# ProPrj__20260317_2026-03-17.net
KiCad netlist of a schematic drawn in EasyEDA Pro
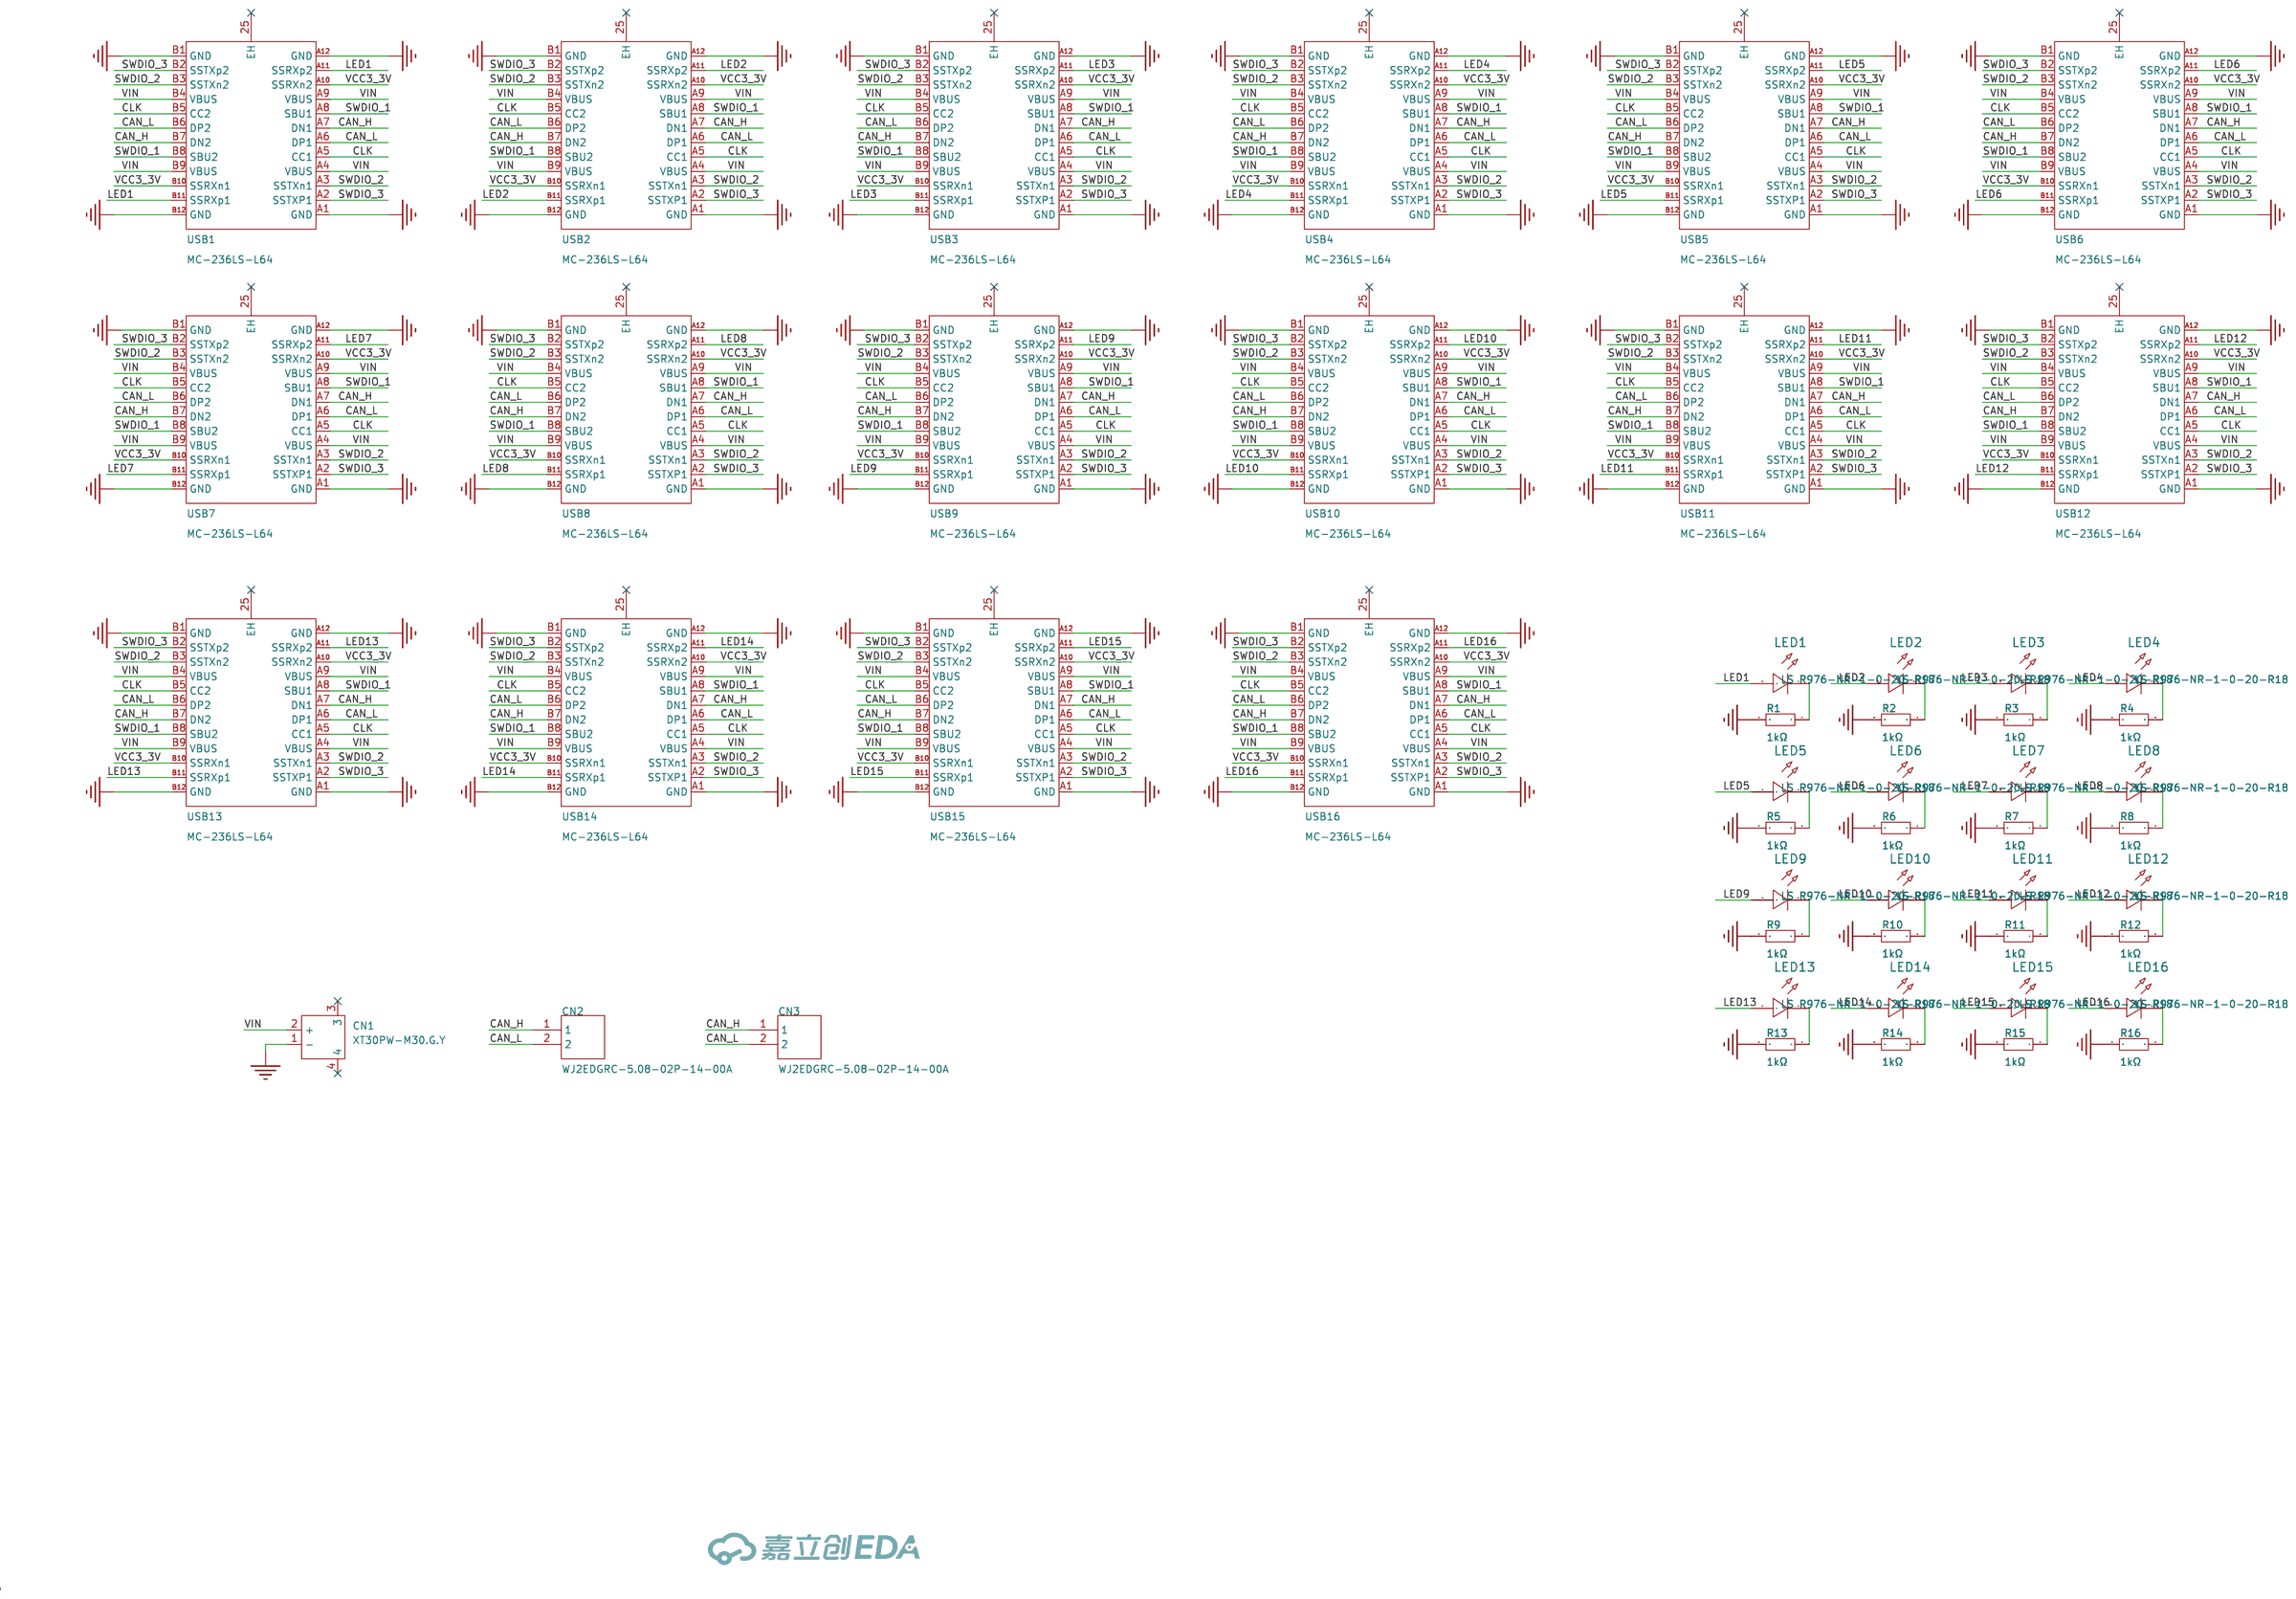
[diagram p0: schematic sheet]

(export (version "E")
  (design (tool "Eeschema 10.0.6"))
  (components
    (comp (ref "CN1")
      (value "XT30PW-M30.G.Y")
      (footprint "easyedapro:CONN-TH_XT30PW-M")
      (description "类别:-;类型1:-;")
      (fields (field (name "Manufacturer") "AMASS(艾迈斯)"))
      (libsource (lib "easyedapro") (part "XT30PW-M"))
    )
    (comp (ref "CN2")
      (value "WJ2EDGRC-5.08-02P-14-00A")
      (footprint "easyedapro:CONN-TH_2P-P5.08_WJ2EDGRC-5.08-2P")
      (fields (field (name "Manufacturer") "KANGNEX(康奈克斯电气)"))
      (libsource (lib "easyedapro") (part "WJ2EDGRC-5.08-2P"))
    )
    (comp (ref "CN3")
      (value "WJ2EDGRC-5.08-02P-14-00A")
      (footprint "easyedapro:CONN-TH_2P-P5.08_WJ2EDGRC-5.08-2P")
      (fields (field (name "Manufacturer") "KANGNEX(康奈克斯电气)"))
      (libsource (lib "easyedapro") (part "WJ2EDGRC-5.08-2P"))
    )
    (comp (ref "LED1")
      (value "LS R976-NR-1-0-20-R18")
      (footprint "easyedapro:LED_0805")
      (fields (field (name "Manufacturer") "OSRAM(欧司朗)"))
      (libsource (lib "easyedapro") (part "LED_R"))
    )
    (comp (ref "LED2")
      (value "LS R976-NR-1-0-20-R18")
      (footprint "easyedapro:LED_0805")
      (fields (field (name "Manufacturer") "OSRAM(欧司朗)"))
      (libsource (lib "easyedapro") (part "LED_R"))
    )
    (comp (ref "LED3")
      (value "LS R976-NR-1-0-20-R18")
      (footprint "easyedapro:LED_0805")
      (fields (field (name "Manufacturer") "OSRAM(欧司朗)"))
      (libsource (lib "easyedapro") (part "LED_R"))
    )
    (comp (ref "LED4")
      (value "LS R976-NR-1-0-20-R18")
      (footprint "easyedapro:LED_0805")
      (fields (field (name "Manufacturer") "OSRAM(欧司朗)"))
      (libsource (lib "easyedapro") (part "LED_R"))
    )
    (comp (ref "LED5")
      (value "LS R976-NR-1-0-20-R18")
      (footprint "easyedapro:LED_0805")
      (fields (field (name "Manufacturer") "OSRAM(欧司朗)"))
      (libsource (lib "easyedapro") (part "LED_R"))
    )
    (comp (ref "LED6")
      (value "LS R976-NR-1-0-20-R18")
      (footprint "easyedapro:LED_0805")
      (fields (field (name "Manufacturer") "OSRAM(欧司朗)"))
      (libsource (lib "easyedapro") (part "LED_R"))
    )
    (comp (ref "LED7")
      (value "LS R976-NR-1-0-20-R18")
      (footprint "easyedapro:LED_0805")
      (fields (field (name "Manufacturer") "OSRAM(欧司朗)"))
      (libsource (lib "easyedapro") (part "LED_R"))
    )
    (comp (ref "LED8")
      (value "LS R976-NR-1-0-20-R18")
      (footprint "easyedapro:LED_0805")
      (fields (field (name "Manufacturer") "OSRAM(欧司朗)"))
      (libsource (lib "easyedapro") (part "LED_R"))
    )
    (comp (ref "LED9")
      (value "LS R976-NR-1-0-20-R18")
      (footprint "easyedapro:LED_0805")
      (fields (field (name "Manufacturer") "OSRAM(欧司朗)"))
      (libsource (lib "easyedapro") (part "LED_R"))
    )
    (comp (ref "LED10")
      (value "LS R976-NR-1-0-20-R18")
      (footprint "easyedapro:LED_0805")
      (fields (field (name "Manufacturer") "OSRAM(欧司朗)"))
      (libsource (lib "easyedapro") (part "LED_R"))
    )
    (comp (ref "LED11")
      (value "LS R976-NR-1-0-20-R18")
      (footprint "easyedapro:LED_0805")
      (fields (field (name "Manufacturer") "OSRAM(欧司朗)"))
      (libsource (lib "easyedapro") (part "LED_R"))
    )
    (comp (ref "LED12")
      (value "LS R976-NR-1-0-20-R18")
      (footprint "easyedapro:LED_0805")
      (fields (field (name "Manufacturer") "OSRAM(欧司朗)"))
      (libsource (lib "easyedapro") (part "LED_R"))
    )
    (comp (ref "LED13")
      (value "LS R976-NR-1-0-20-R18")
      (footprint "easyedapro:LED_0805")
      (fields (field (name "Manufacturer") "OSRAM(欧司朗)"))
      (libsource (lib "easyedapro") (part "LED_R"))
    )
    (comp (ref "LED14")
      (value "LS R976-NR-1-0-20-R18")
      (footprint "easyedapro:LED_0805")
      (fields (field (name "Manufacturer") "OSRAM(欧司朗)"))
      (libsource (lib "easyedapro") (part "LED_R"))
    )
    (comp (ref "LED15")
      (value "LS R976-NR-1-0-20-R18")
      (footprint "easyedapro:LED_0805")
      (fields (field (name "Manufacturer") "OSRAM(欧司朗)"))
      (libsource (lib "easyedapro") (part "LED_R"))
    )
    (comp (ref "LED16")
      (value "LS R976-NR-1-0-20-R18")
      (footprint "easyedapro:LED_0805")
      (fields (field (name "Manufacturer") "OSRAM(欧司朗)"))
      (libsource (lib "easyedapro") (part "LED_R"))
    )
    (comp (ref "R1")
      (value "1kΩ")
      (footprint "easyedapro:R0805")
      (fields
        (field (name "Manufacturer Part") "0805W8F1001T5E")
        (field (name "Manufacturer") "UNI-ROYAL(厚声)")
      )
      (libsource (lib "easyedapro") (part "电阻"))
    )
    (comp (ref "R2")
      (value "1kΩ")
      (footprint "easyedapro:R0805")
      (fields
        (field (name "Manufacturer Part") "0805W8F1001T5E")
        (field (name "Manufacturer") "UNI-ROYAL(厚声)")
      )
      (libsource (lib "easyedapro") (part "电阻"))
    )
    (comp (ref "R3")
      (value "1kΩ")
      (footprint "easyedapro:R0805")
      (fields
        (field (name "Manufacturer Part") "0805W8F1001T5E")
        (field (name "Manufacturer") "UNI-ROYAL(厚声)")
      )
      (libsource (lib "easyedapro") (part "电阻"))
    )
    (comp (ref "R4")
      (value "1kΩ")
      (footprint "easyedapro:R0805")
      (fields
        (field (name "Manufacturer Part") "0805W8F1001T5E")
        (field (name "Manufacturer") "UNI-ROYAL(厚声)")
      )
      (libsource (lib "easyedapro") (part "电阻"))
    )
    (comp (ref "R5")
      (value "1kΩ")
      (footprint "easyedapro:R0805")
      (fields
        (field (name "Manufacturer Part") "0805W8F1001T5E")
        (field (name "Manufacturer") "UNI-ROYAL(厚声)")
      )
      (libsource (lib "easyedapro") (part "电阻"))
    )
    (comp (ref "R6")
      (value "1kΩ")
      (footprint "easyedapro:R0805")
      (fields
        (field (name "Manufacturer Part") "0805W8F1001T5E")
        (field (name "Manufacturer") "UNI-ROYAL(厚声)")
      )
      (libsource (lib "easyedapro") (part "电阻"))
    )
    (comp (ref "R7")
      (value "1kΩ")
      (footprint "easyedapro:R0805")
      (fields
        (field (name "Manufacturer Part") "0805W8F1001T5E")
        (field (name "Manufacturer") "UNI-ROYAL(厚声)")
      )
      (libsource (lib "easyedapro") (part "电阻"))
    )
    (comp (ref "R8")
      (value "1kΩ")
      (footprint "easyedapro:R0805")
      (fields
        (field (name "Manufacturer Part") "0805W8F1001T5E")
        (field (name "Manufacturer") "UNI-ROYAL(厚声)")
      )
      (libsource (lib "easyedapro") (part "电阻"))
    )
    (comp (ref "R9")
      (value "1kΩ")
      (footprint "easyedapro:R0805")
      (fields
        (field (name "Manufacturer Part") "0805W8F1001T5E")
        (field (name "Manufacturer") "UNI-ROYAL(厚声)")
      )
      (libsource (lib "easyedapro") (part "电阻"))
    )
    (comp (ref "R10")
      (value "1kΩ")
      (footprint "easyedapro:R0805")
      (fields
        (field (name "Manufacturer Part") "0805W8F1001T5E")
        (field (name "Manufacturer") "UNI-ROYAL(厚声)")
      )
      (libsource (lib "easyedapro") (part "电阻"))
    )
    (comp (ref "R11")
      (value "1kΩ")
      (footprint "easyedapro:R0805")
      (fields
        (field (name "Manufacturer Part") "0805W8F1001T5E")
        (field (name "Manufacturer") "UNI-ROYAL(厚声)")
      )
      (libsource (lib "easyedapro") (part "电阻"))
    )
    (comp (ref "R12")
      (value "1kΩ")
      (footprint "easyedapro:R0805")
      (fields
        (field (name "Manufacturer Part") "0805W8F1001T5E")
        (field (name "Manufacturer") "UNI-ROYAL(厚声)")
      )
      (libsource (lib "easyedapro") (part "电阻"))
    )
    (comp (ref "R13")
      (value "1kΩ")
      (footprint "easyedapro:R0805")
      (fields
        (field (name "Manufacturer Part") "0805W8F1001T5E")
        (field (name "Manufacturer") "UNI-ROYAL(厚声)")
      )
      (libsource (lib "easyedapro") (part "电阻"))
    )
    (comp (ref "R14")
      (value "1kΩ")
      (footprint "easyedapro:R0805")
      (fields
        (field (name "Manufacturer Part") "0805W8F1001T5E")
        (field (name "Manufacturer") "UNI-ROYAL(厚声)")
      )
      (libsource (lib "easyedapro") (part "电阻"))
    )
    (comp (ref "R15")
      (value "1kΩ")
      (footprint "easyedapro:R0805")
      (fields
        (field (name "Manufacturer Part") "0805W8F1001T5E")
        (field (name "Manufacturer") "UNI-ROYAL(厚声)")
      )
      (libsource (lib "easyedapro") (part "电阻"))
    )
    (comp (ref "R16")
      (value "1kΩ")
      (footprint "easyedapro:R0805")
      (fields
        (field (name "Manufacturer Part") "0805W8F1001T5E")
        (field (name "Manufacturer") "UNI-ROYAL(厚声)")
      )
      (libsource (lib "easyedapro") (part "电阻"))
    )
    (comp (ref "USB1")
      (value "MC-236LS-L64")
      (footprint "easyedapro:TYPE-C-USB-SMD_TYPE-C-31-M-06")
      (description "连接器类型:Type-C;协议标准:USB 3.1;公母:母;安装方式:立贴;触点数量:24P;端口数量:1;额定电流 - 电源:5A;工作温度:-25°C~+85°C;")
      (fields (field (name "Manufacturer") "HANBO(汉博)"))
      (libsource (lib "easyedapro") (part "MC-236LS-L64"))
    )
    (comp (ref "USB2")
      (value "MC-236LS-L64")
      (footprint "easyedapro:TYPE-C-USB-SMD_TYPE-C-31-M-06")
      (description "连接器类型:Type-C;协议标准:USB 3.1;公母:母;安装方式:立贴;触点数量:24P;端口数量:1;额定电流 - 电源:5A;工作温度:-25°C~+85°C;")
      (fields (field (name "Manufacturer") "HANBO(汉博)"))
      (libsource (lib "easyedapro") (part "MC-236LS-L64"))
    )
    (comp (ref "USB3")
      (value "MC-236LS-L64")
      (footprint "easyedapro:TYPE-C-USB-SMD_TYPE-C-31-M-06")
      (description "连接器类型:Type-C;协议标准:USB 3.1;公母:母;安装方式:立贴;触点数量:24P;端口数量:1;额定电流 - 电源:5A;工作温度:-25°C~+85°C;")
      (fields (field (name "Manufacturer") "HANBO(汉博)"))
      (libsource (lib "easyedapro") (part "MC-236LS-L64"))
    )
    (comp (ref "USB4")
      (value "MC-236LS-L64")
      (footprint "easyedapro:TYPE-C-USB-SMD_TYPE-C-31-M-06")
      (description "连接器类型:Type-C;协议标准:USB 3.1;公母:母;安装方式:立贴;触点数量:24P;端口数量:1;额定电流 - 电源:5A;工作温度:-25°C~+85°C;")
      (fields (field (name "Manufacturer") "HANBO(汉博)"))
      (libsource (lib "easyedapro") (part "MC-236LS-L64"))
    )
    (comp (ref "USB5")
      (value "MC-236LS-L64")
      (footprint "easyedapro:TYPE-C-USB-SMD_TYPE-C-31-M-06")
      (description "连接器类型:Type-C;协议标准:USB 3.1;公母:母;安装方式:立贴;触点数量:24P;端口数量:1;额定电流 - 电源:5A;工作温度:-25°C~+85°C;")
      (fields (field (name "Manufacturer") "HANBO(汉博)"))
      (libsource (lib "easyedapro") (part "MC-236LS-L64"))
    )
    (comp (ref "USB6")
      (value "MC-236LS-L64")
      (footprint "easyedapro:TYPE-C-USB-SMD_TYPE-C-31-M-06")
      (description "连接器类型:Type-C;协议标准:USB 3.1;公母:母;安装方式:立贴;触点数量:24P;端口数量:1;额定电流 - 电源:5A;工作温度:-25°C~+85°C;")
      (fields (field (name "Manufacturer") "HANBO(汉博)"))
      (libsource (lib "easyedapro") (part "MC-236LS-L64"))
    )
    (comp (ref "USB7")
      (value "MC-236LS-L64")
      (footprint "easyedapro:TYPE-C-USB-SMD_TYPE-C-31-M-06")
      (description "连接器类型:Type-C;协议标准:USB 3.1;公母:母;安装方式:立贴;触点数量:24P;端口数量:1;额定电流 - 电源:5A;工作温度:-25°C~+85°C;")
      (fields (field (name "Manufacturer") "HANBO(汉博)"))
      (libsource (lib "easyedapro") (part "MC-236LS-L64"))
    )
    (comp (ref "USB8")
      (value "MC-236LS-L64")
      (footprint "easyedapro:TYPE-C-USB-SMD_TYPE-C-31-M-06")
      (description "连接器类型:Type-C;协议标准:USB 3.1;公母:母;安装方式:立贴;触点数量:24P;端口数量:1;额定电流 - 电源:5A;工作温度:-25°C~+85°C;")
      (fields (field (name "Manufacturer") "HANBO(汉博)"))
      (libsource (lib "easyedapro") (part "MC-236LS-L64"))
    )
    (comp (ref "USB9")
      (value "MC-236LS-L64")
      (footprint "easyedapro:TYPE-C-USB-SMD_TYPE-C-31-M-06")
      (description "连接器类型:Type-C;协议标准:USB 3.1;公母:母;安装方式:立贴;触点数量:24P;端口数量:1;额定电流 - 电源:5A;工作温度:-25°C~+85°C;")
      (fields (field (name "Manufacturer") "HANBO(汉博)"))
      (libsource (lib "easyedapro") (part "MC-236LS-L64"))
    )
    (comp (ref "USB10")
      (value "MC-236LS-L64")
      (footprint "easyedapro:TYPE-C-USB-SMD_TYPE-C-31-M-06")
      (description "连接器类型:Type-C;协议标准:USB 3.1;公母:母;安装方式:立贴;触点数量:24P;端口数量:1;额定电流 - 电源:5A;工作温度:-25°C~+85°C;")
      (fields (field (name "Manufacturer") "HANBO(汉博)"))
      (libsource (lib "easyedapro") (part "MC-236LS-L64"))
    )
    (comp (ref "USB11")
      (value "MC-236LS-L64")
      (footprint "easyedapro:TYPE-C-USB-SMD_TYPE-C-31-M-06")
      (description "连接器类型:Type-C;协议标准:USB 3.1;公母:母;安装方式:立贴;触点数量:24P;端口数量:1;额定电流 - 电源:5A;工作温度:-25°C~+85°C;")
      (fields (field (name "Manufacturer") "HANBO(汉博)"))
      (libsource (lib "easyedapro") (part "MC-236LS-L64"))
    )
    (comp (ref "USB12")
      (value "MC-236LS-L64")
      (footprint "easyedapro:TYPE-C-USB-SMD_TYPE-C-31-M-06")
      (description "连接器类型:Type-C;协议标准:USB 3.1;公母:母;安装方式:立贴;触点数量:24P;端口数量:1;额定电流 - 电源:5A;工作温度:-25°C~+85°C;")
      (fields (field (name "Manufacturer") "HANBO(汉博)"))
      (libsource (lib "easyedapro") (part "MC-236LS-L64"))
    )
    (comp (ref "USB13")
      (value "MC-236LS-L64")
      (footprint "easyedapro:TYPE-C-USB-SMD_TYPE-C-31-M-06")
      (description "连接器类型:Type-C;协议标准:USB 3.1;公母:母;安装方式:立贴;触点数量:24P;端口数量:1;额定电流 - 电源:5A;工作温度:-25°C~+85°C;")
      (fields (field (name "Manufacturer") "HANBO(汉博)"))
      (libsource (lib "easyedapro") (part "MC-236LS-L64"))
    )
    (comp (ref "USB14")
      (value "MC-236LS-L64")
      (footprint "easyedapro:TYPE-C-USB-SMD_TYPE-C-31-M-06")
      (description "连接器类型:Type-C;协议标准:USB 3.1;公母:母;安装方式:立贴;触点数量:24P;端口数量:1;额定电流 - 电源:5A;工作温度:-25°C~+85°C;")
      (fields (field (name "Manufacturer") "HANBO(汉博)"))
      (libsource (lib "easyedapro") (part "MC-236LS-L64"))
    )
    (comp (ref "USB15")
      (value "MC-236LS-L64")
      (footprint "easyedapro:TYPE-C-USB-SMD_TYPE-C-31-M-06")
      (description "连接器类型:Type-C;协议标准:USB 3.1;公母:母;安装方式:立贴;触点数量:24P;端口数量:1;额定电流 - 电源:5A;工作温度:-25°C~+85°C;")
      (fields (field (name "Manufacturer") "HANBO(汉博)"))
      (libsource (lib "easyedapro") (part "MC-236LS-L64"))
    )
    (comp (ref "USB16")
      (value "MC-236LS-L64")
      (footprint "easyedapro:TYPE-C-USB-SMD_TYPE-C-31-M-06")
      (description "连接器类型:Type-C;协议标准:USB 3.1;公母:母;安装方式:立贴;触点数量:24P;端口数量:1;额定电流 - 电源:5A;工作温度:-25°C~+85°C;")
      (fields (field (name "Manufacturer") "HANBO(汉博)"))
      (libsource (lib "easyedapro") (part "MC-236LS-L64"))
    )
  )
  (nets
    (net (code "1") (name "/CAN_H") (class "Default")
      (node (ref "CN2") (pin "1") (pinfunction "1_1") (pintype "unspecified"))
      (node (ref "CN3") (pin "1") (pinfunction "1_1") (pintype "unspecified"))
      (node (ref "USB1") (pin "A7") (pinfunction "DN1_A7") (pintype "unspecified"))
      (node (ref "USB1") (pin "B7") (pinfunction "DN2_B7") (pintype "unspecified"))
      (node (ref "USB10") (pin "A7") (pinfunction "DN1_A7") (pintype "unspecified"))
      (node (ref "USB10") (pin "B7") (pinfunction "DN2_B7") (pintype "unspecified"))
      (node (ref "USB11") (pin "A7") (pinfunction "DN1_A7") (pintype "unspecified"))
      (node (ref "USB11") (pin "B7") (pinfunction "DN2_B7") (pintype "unspecified"))
      (node (ref "USB12") (pin "A7") (pinfunction "DN1_A7") (pintype "unspecified"))
      (node (ref "USB12") (pin "B7") (pinfunction "DN2_B7") (pintype "unspecified"))
      (node (ref "USB13") (pin "A7") (pinfunction "DN1_A7") (pintype "unspecified"))
      (node (ref "USB13") (pin "B7") (pinfunction "DN2_B7") (pintype "unspecified"))
      (node (ref "USB14") (pin "A7") (pinfunction "DN1_A7") (pintype "unspecified"))
      (node (ref "USB14") (pin "B7") (pinfunction "DN2_B7") (pintype "unspecified"))
      (node (ref "USB15") (pin "A7") (pinfunction "DN1_A7") (pintype "unspecified"))
      (node (ref "USB15") (pin "B7") (pinfunction "DN2_B7") (pintype "unspecified"))
      (node (ref "USB16") (pin "A7") (pinfunction "DN1_A7") (pintype "unspecified"))
      (node (ref "USB16") (pin "B7") (pinfunction "DN2_B7") (pintype "unspecified"))
      (node (ref "USB2") (pin "A7") (pinfunction "DN1_A7") (pintype "unspecified"))
      (node (ref "USB2") (pin "B7") (pinfunction "DN2_B7") (pintype "unspecified"))
      (node (ref "USB3") (pin "A7") (pinfunction "DN1_A7") (pintype "unspecified"))
      (node (ref "USB3") (pin "B7") (pinfunction "DN2_B7") (pintype "unspecified"))
      (node (ref "USB4") (pin "A7") (pinfunction "DN1_A7") (pintype "unspecified"))
      (node (ref "USB4") (pin "B7") (pinfunction "DN2_B7") (pintype "unspecified"))
      (node (ref "USB5") (pin "A7") (pinfunction "DN1_A7") (pintype "unspecified"))
      (node (ref "USB5") (pin "B7") (pinfunction "DN2_B7") (pintype "unspecified"))
      (node (ref "USB6") (pin "A7") (pinfunction "DN1_A7") (pintype "unspecified"))
      (node (ref "USB6") (pin "B7") (pinfunction "DN2_B7") (pintype "unspecified"))
      (node (ref "USB7") (pin "A7") (pinfunction "DN1_A7") (pintype "unspecified"))
      (node (ref "USB7") (pin "B7") (pinfunction "DN2_B7") (pintype "unspecified"))
      (node (ref "USB8") (pin "A7") (pinfunction "DN1_A7") (pintype "unspecified"))
      (node (ref "USB8") (pin "B7") (pinfunction "DN2_B7") (pintype "unspecified"))
      (node (ref "USB9") (pin "A7") (pinfunction "DN1_A7") (pintype "unspecified"))
      (node (ref "USB9") (pin "B7") (pinfunction "DN2_B7") (pintype "unspecified"))
    )
    (net (code "2") (name "/CAN_L") (class "Default")
      (node (ref "CN2") (pin "2") (pinfunction "2_2") (pintype "unspecified"))
      (node (ref "CN3") (pin "2") (pinfunction "2_2") (pintype "unspecified"))
      (node (ref "USB1") (pin "A6") (pinfunction "DP1_A6") (pintype "unspecified"))
      (node (ref "USB1") (pin "B6") (pinfunction "DP2_B6") (pintype "unspecified"))
      (node (ref "USB10") (pin "A6") (pinfunction "DP1_A6") (pintype "unspecified"))
      (node (ref "USB10") (pin "B6") (pinfunction "DP2_B6") (pintype "unspecified"))
      (node (ref "USB11") (pin "A6") (pinfunction "DP1_A6") (pintype "unspecified"))
      (node (ref "USB11") (pin "B6") (pinfunction "DP2_B6") (pintype "unspecified"))
      (node (ref "USB12") (pin "A6") (pinfunction "DP1_A6") (pintype "unspecified"))
      (node (ref "USB12") (pin "B6") (pinfunction "DP2_B6") (pintype "unspecified"))
      (node (ref "USB13") (pin "A6") (pinfunction "DP1_A6") (pintype "unspecified"))
      (node (ref "USB13") (pin "B6") (pinfunction "DP2_B6") (pintype "unspecified"))
      (node (ref "USB14") (pin "A6") (pinfunction "DP1_A6") (pintype "unspecified"))
      (node (ref "USB14") (pin "B6") (pinfunction "DP2_B6") (pintype "unspecified"))
      (node (ref "USB15") (pin "A6") (pinfunction "DP1_A6") (pintype "unspecified"))
      (node (ref "USB15") (pin "B6") (pinfunction "DP2_B6") (pintype "unspecified"))
      (node (ref "USB16") (pin "A6") (pinfunction "DP1_A6") (pintype "unspecified"))
      (node (ref "USB16") (pin "B6") (pinfunction "DP2_B6") (pintype "unspecified"))
      (node (ref "USB2") (pin "A6") (pinfunction "DP1_A6") (pintype "unspecified"))
      (node (ref "USB2") (pin "B6") (pinfunction "DP2_B6") (pintype "unspecified"))
      (node (ref "USB3") (pin "A6") (pinfunction "DP1_A6") (pintype "unspecified"))
      (node (ref "USB3") (pin "B6") (pinfunction "DP2_B6") (pintype "unspecified"))
      (node (ref "USB4") (pin "A6") (pinfunction "DP1_A6") (pintype "unspecified"))
      (node (ref "USB4") (pin "B6") (pinfunction "DP2_B6") (pintype "unspecified"))
      (node (ref "USB5") (pin "A6") (pinfunction "DP1_A6") (pintype "unspecified"))
      (node (ref "USB5") (pin "B6") (pinfunction "DP2_B6") (pintype "unspecified"))
      (node (ref "USB6") (pin "A6") (pinfunction "DP1_A6") (pintype "unspecified"))
      (node (ref "USB6") (pin "B6") (pinfunction "DP2_B6") (pintype "unspecified"))
      (node (ref "USB7") (pin "A6") (pinfunction "DP1_A6") (pintype "unspecified"))
      (node (ref "USB7") (pin "B6") (pinfunction "DP2_B6") (pintype "unspecified"))
      (node (ref "USB8") (pin "A6") (pinfunction "DP1_A6") (pintype "unspecified"))
      (node (ref "USB8") (pin "B6") (pinfunction "DP2_B6") (pintype "unspecified"))
      (node (ref "USB9") (pin "A6") (pinfunction "DP1_A6") (pintype "unspecified"))
      (node (ref "USB9") (pin "B6") (pinfunction "DP2_B6") (pintype "unspecified"))
    )
    (net (code "3") (name "/CLK") (class "Default")
      (node (ref "USB1") (pin "A5") (pinfunction "CC1_A5") (pintype "unspecified"))
      (node (ref "USB1") (pin "B5") (pinfunction "CC2_B5") (pintype "unspecified"))
      (node (ref "USB10") (pin "A5") (pinfunction "CC1_A5") (pintype "unspecified"))
      (node (ref "USB10") (pin "B5") (pinfunction "CC2_B5") (pintype "unspecified"))
      (node (ref "USB11") (pin "A5") (pinfunction "CC1_A5") (pintype "unspecified"))
      (node (ref "USB11") (pin "B5") (pinfunction "CC2_B5") (pintype "unspecified"))
      (node (ref "USB12") (pin "A5") (pinfunction "CC1_A5") (pintype "unspecified"))
      (node (ref "USB12") (pin "B5") (pinfunction "CC2_B5") (pintype "unspecified"))
      (node (ref "USB13") (pin "A5") (pinfunction "CC1_A5") (pintype "unspecified"))
      (node (ref "USB13") (pin "B5") (pinfunction "CC2_B5") (pintype "unspecified"))
      (node (ref "USB14") (pin "A5") (pinfunction "CC1_A5") (pintype "unspecified"))
      (node (ref "USB14") (pin "B5") (pinfunction "CC2_B5") (pintype "unspecified"))
      (node (ref "USB15") (pin "A5") (pinfunction "CC1_A5") (pintype "unspecified"))
      (node (ref "USB15") (pin "B5") (pinfunction "CC2_B5") (pintype "unspecified"))
      (node (ref "USB16") (pin "A5") (pinfunction "CC1_A5") (pintype "unspecified"))
      (node (ref "USB16") (pin "B5") (pinfunction "CC2_B5") (pintype "unspecified"))
      (node (ref "USB2") (pin "A5") (pinfunction "CC1_A5") (pintype "unspecified"))
      (node (ref "USB2") (pin "B5") (pinfunction "CC2_B5") (pintype "unspecified"))
      (node (ref "USB3") (pin "A5") (pinfunction "CC1_A5") (pintype "unspecified"))
      (node (ref "USB3") (pin "B5") (pinfunction "CC2_B5") (pintype "unspecified"))
      (node (ref "USB4") (pin "A5") (pinfunction "CC1_A5") (pintype "unspecified"))
      (node (ref "USB4") (pin "B5") (pinfunction "CC2_B5") (pintype "unspecified"))
      (node (ref "USB5") (pin "A5") (pinfunction "CC1_A5") (pintype "unspecified"))
      (node (ref "USB5") (pin "B5") (pinfunction "CC2_B5") (pintype "unspecified"))
      (node (ref "USB6") (pin "A5") (pinfunction "CC1_A5") (pintype "unspecified"))
      (node (ref "USB6") (pin "B5") (pinfunction "CC2_B5") (pintype "unspecified"))
      (node (ref "USB7") (pin "A5") (pinfunction "CC1_A5") (pintype "unspecified"))
      (node (ref "USB7") (pin "B5") (pinfunction "CC2_B5") (pintype "unspecified"))
      (node (ref "USB8") (pin "A5") (pinfunction "CC1_A5") (pintype "unspecified"))
      (node (ref "USB8") (pin "B5") (pinfunction "CC2_B5") (pintype "unspecified"))
      (node (ref "USB9") (pin "A5") (pinfunction "CC1_A5") (pintype "unspecified"))
      (node (ref "USB9") (pin "B5") (pinfunction "CC2_B5") (pintype "unspecified"))
    )
    (net (code "4") (name "/LED1") (class "Default")
      (node (ref "LED1") (pin "2") (pinfunction "A_2") (pintype "input"))
      (node (ref "USB1") (pin "A11") (pinfunction "SSRXp2_A11") (pintype "unspecified"))
      (node (ref "USB1") (pin "B11") (pinfunction "SSRXp1_B11") (pintype "unspecified"))
    )
    (net (code "5") (name "/LED2") (class "Default")
      (node (ref "LED2") (pin "2") (pinfunction "A_2") (pintype "input"))
      (node (ref "USB2") (pin "A11") (pinfunction "SSRXp2_A11") (pintype "unspecified"))
      (node (ref "USB2") (pin "B11") (pinfunction "SSRXp1_B11") (pintype "unspecified"))
    )
    (net (code "6") (name "/LED3") (class "Default")
      (node (ref "LED3") (pin "2") (pinfunction "A_2") (pintype "input"))
      (node (ref "USB3") (pin "A11") (pinfunction "SSRXp2_A11") (pintype "unspecified"))
      (node (ref "USB3") (pin "B11") (pinfunction "SSRXp1_B11") (pintype "unspecified"))
    )
    (net (code "7") (name "/LED4") (class "Default")
      (node (ref "LED4") (pin "2") (pinfunction "A_2") (pintype "input"))
      (node (ref "USB4") (pin "A11") (pinfunction "SSRXp2_A11") (pintype "unspecified"))
      (node (ref "USB4") (pin "B11") (pinfunction "SSRXp1_B11") (pintype "unspecified"))
    )
    (net (code "8") (name "/LED5") (class "Default")
      (node (ref "LED5") (pin "2") (pinfunction "A_2") (pintype "input"))
      (node (ref "USB5") (pin "A11") (pinfunction "SSRXp2_A11") (pintype "unspecified"))
      (node (ref "USB5") (pin "B11") (pinfunction "SSRXp1_B11") (pintype "unspecified"))
    )
    (net (code "9") (name "/LED6") (class "Default")
      (node (ref "LED6") (pin "2") (pinfunction "A_2") (pintype "input"))
      (node (ref "USB6") (pin "A11") (pinfunction "SSRXp2_A11") (pintype "unspecified"))
      (node (ref "USB6") (pin "B11") (pinfunction "SSRXp1_B11") (pintype "unspecified"))
    )
    (net (code "10") (name "/LED7") (class "Default")
      (node (ref "LED7") (pin "2") (pinfunction "A_2") (pintype "input"))
      (node (ref "USB7") (pin "A11") (pinfunction "SSRXp2_A11") (pintype "unspecified"))
      (node (ref "USB7") (pin "B11") (pinfunction "SSRXp1_B11") (pintype "unspecified"))
    )
    (net (code "11") (name "/LED8") (class "Default")
      (node (ref "LED8") (pin "2") (pinfunction "A_2") (pintype "input"))
      (node (ref "USB8") (pin "A11") (pinfunction "SSRXp2_A11") (pintype "unspecified"))
      (node (ref "USB8") (pin "B11") (pinfunction "SSRXp1_B11") (pintype "unspecified"))
    )
    (net (code "12") (name "/LED9") (class "Default")
      (node (ref "LED9") (pin "2") (pinfunction "A_2") (pintype "input"))
      (node (ref "USB9") (pin "A11") (pinfunction "SSRXp2_A11") (pintype "unspecified"))
      (node (ref "USB9") (pin "B11") (pinfunction "SSRXp1_B11") (pintype "unspecified"))
    )
    (net (code "13") (name "/LED10") (class "Default")
      (node (ref "LED10") (pin "2") (pinfunction "A_2") (pintype "input"))
      (node (ref "USB10") (pin "A11") (pinfunction "SSRXp2_A11") (pintype "unspecified"))
      (node (ref "USB10") (pin "B11") (pinfunction "SSRXp1_B11") (pintype "unspecified"))
    )
    (net (code "14") (name "/LED11") (class "Default")
      (node (ref "LED11") (pin "2") (pinfunction "A_2") (pintype "input"))
      (node (ref "USB11") (pin "A11") (pinfunction "SSRXp2_A11") (pintype "unspecified"))
      (node (ref "USB11") (pin "B11") (pinfunction "SSRXp1_B11") (pintype "unspecified"))
    )
    (net (code "15") (name "/LED12") (class "Default")
      (node (ref "LED12") (pin "2") (pinfunction "A_2") (pintype "input"))
      (node (ref "USB12") (pin "A11") (pinfunction "SSRXp2_A11") (pintype "unspecified"))
      (node (ref "USB12") (pin "B11") (pinfunction "SSRXp1_B11") (pintype "unspecified"))
    )
    (net (code "16") (name "/LED13") (class "Default")
      (node (ref "LED13") (pin "2") (pinfunction "A_2") (pintype "input"))
      (node (ref "USB13") (pin "A11") (pinfunction "SSRXp2_A11") (pintype "unspecified"))
      (node (ref "USB13") (pin "B11") (pinfunction "SSRXp1_B11") (pintype "unspecified"))
    )
    (net (code "17") (name "/LED14") (class "Default")
      (node (ref "LED14") (pin "2") (pinfunction "A_2") (pintype "input"))
      (node (ref "USB14") (pin "A11") (pinfunction "SSRXp2_A11") (pintype "unspecified"))
      (node (ref "USB14") (pin "B11") (pinfunction "SSRXp1_B11") (pintype "unspecified"))
    )
    (net (code "18") (name "/LED15") (class "Default")
      (node (ref "LED15") (pin "2") (pinfunction "A_2") (pintype "input"))
      (node (ref "USB15") (pin "A11") (pinfunction "SSRXp2_A11") (pintype "unspecified"))
      (node (ref "USB15") (pin "B11") (pinfunction "SSRXp1_B11") (pintype "unspecified"))
    )
    (net (code "19") (name "/LED16") (class "Default")
      (node (ref "LED16") (pin "2") (pinfunction "A_2") (pintype "input"))
      (node (ref "USB16") (pin "A11") (pinfunction "SSRXp2_A11") (pintype "unspecified"))
      (node (ref "USB16") (pin "B11") (pinfunction "SSRXp1_B11") (pintype "unspecified"))
    )
    (net (code "20") (name "/SWDIO_1") (class "Default")
      (node (ref "USB1") (pin "A8") (pinfunction "SBU1_A8") (pintype "unspecified"))
      (node (ref "USB1") (pin "B8") (pinfunction "SBU2_B8") (pintype "unspecified"))
      (node (ref "USB10") (pin "A8") (pinfunction "SBU1_A8") (pintype "unspecified"))
      (node (ref "USB10") (pin "B8") (pinfunction "SBU2_B8") (pintype "unspecified"))
      (node (ref "USB11") (pin "A8") (pinfunction "SBU1_A8") (pintype "unspecified"))
      (node (ref "USB11") (pin "B8") (pinfunction "SBU2_B8") (pintype "unspecified"))
      (node (ref "USB12") (pin "A8") (pinfunction "SBU1_A8") (pintype "unspecified"))
      (node (ref "USB12") (pin "B8") (pinfunction "SBU2_B8") (pintype "unspecified"))
      (node (ref "USB13") (pin "A8") (pinfunction "SBU1_A8") (pintype "unspecified"))
      (node (ref "USB13") (pin "B8") (pinfunction "SBU2_B8") (pintype "unspecified"))
      (node (ref "USB14") (pin "A8") (pinfunction "SBU1_A8") (pintype "unspecified"))
      (node (ref "USB14") (pin "B8") (pinfunction "SBU2_B8") (pintype "unspecified"))
      (node (ref "USB15") (pin "A8") (pinfunction "SBU1_A8") (pintype "unspecified"))
      (node (ref "USB15") (pin "B8") (pinfunction "SBU2_B8") (pintype "unspecified"))
      (node (ref "USB16") (pin "A8") (pinfunction "SBU1_A8") (pintype "unspecified"))
      (node (ref "USB16") (pin "B8") (pinfunction "SBU2_B8") (pintype "unspecified"))
      (node (ref "USB2") (pin "A8") (pinfunction "SBU1_A8") (pintype "unspecified"))
      (node (ref "USB2") (pin "B8") (pinfunction "SBU2_B8") (pintype "unspecified"))
      (node (ref "USB3") (pin "A8") (pinfunction "SBU1_A8") (pintype "unspecified"))
      (node (ref "USB3") (pin "B8") (pinfunction "SBU2_B8") (pintype "unspecified"))
      (node (ref "USB4") (pin "A8") (pinfunction "SBU1_A8") (pintype "unspecified"))
      (node (ref "USB4") (pin "B8") (pinfunction "SBU2_B8") (pintype "unspecified"))
      (node (ref "USB5") (pin "A8") (pinfunction "SBU1_A8") (pintype "unspecified"))
      (node (ref "USB5") (pin "B8") (pinfunction "SBU2_B8") (pintype "unspecified"))
      (node (ref "USB6") (pin "A8") (pinfunction "SBU1_A8") (pintype "unspecified"))
      (node (ref "USB6") (pin "B8") (pinfunction "SBU2_B8") (pintype "unspecified"))
      (node (ref "USB7") (pin "A8") (pinfunction "SBU1_A8") (pintype "unspecified"))
      (node (ref "USB7") (pin "B8") (pinfunction "SBU2_B8") (pintype "unspecified"))
      (node (ref "USB8") (pin "A8") (pinfunction "SBU1_A8") (pintype "unspecified"))
      (node (ref "USB8") (pin "B8") (pinfunction "SBU2_B8") (pintype "unspecified"))
      (node (ref "USB9") (pin "A8") (pinfunction "SBU1_A8") (pintype "unspecified"))
      (node (ref "USB9") (pin "B8") (pinfunction "SBU2_B8") (pintype "unspecified"))
    )
    (net (code "21") (name "/SWDIO_2") (class "Default")
      (node (ref "USB1") (pin "A3") (pinfunction "SSTXn1_A3") (pintype "unspecified"))
      (node (ref "USB1") (pin "B3") (pinfunction "SSTXn2_B3") (pintype "unspecified"))
      (node (ref "USB10") (pin "A3") (pinfunction "SSTXn1_A3") (pintype "unspecified"))
      (node (ref "USB10") (pin "B3") (pinfunction "SSTXn2_B3") (pintype "unspecified"))
      (node (ref "USB11") (pin "A3") (pinfunction "SSTXn1_A3") (pintype "unspecified"))
      (node (ref "USB11") (pin "B3") (pinfunction "SSTXn2_B3") (pintype "unspecified"))
      (node (ref "USB12") (pin "A3") (pinfunction "SSTXn1_A3") (pintype "unspecified"))
      (node (ref "USB12") (pin "B3") (pinfunction "SSTXn2_B3") (pintype "unspecified"))
      (node (ref "USB13") (pin "A3") (pinfunction "SSTXn1_A3") (pintype "unspecified"))
      (node (ref "USB13") (pin "B3") (pinfunction "SSTXn2_B3") (pintype "unspecified"))
      (node (ref "USB14") (pin "A3") (pinfunction "SSTXn1_A3") (pintype "unspecified"))
      (node (ref "USB14") (pin "B3") (pinfunction "SSTXn2_B3") (pintype "unspecified"))
      (node (ref "USB15") (pin "A3") (pinfunction "SSTXn1_A3") (pintype "unspecified"))
      (node (ref "USB15") (pin "B3") (pinfunction "SSTXn2_B3") (pintype "unspecified"))
      (node (ref "USB16") (pin "A3") (pinfunction "SSTXn1_A3") (pintype "unspecified"))
      (node (ref "USB16") (pin "B3") (pinfunction "SSTXn2_B3") (pintype "unspecified"))
      (node (ref "USB2") (pin "A3") (pinfunction "SSTXn1_A3") (pintype "unspecified"))
      (node (ref "USB2") (pin "B3") (pinfunction "SSTXn2_B3") (pintype "unspecified"))
      (node (ref "USB3") (pin "A3") (pinfunction "SSTXn1_A3") (pintype "unspecified"))
      (node (ref "USB3") (pin "B3") (pinfunction "SSTXn2_B3") (pintype "unspecified"))
      (node (ref "USB4") (pin "A3") (pinfunction "SSTXn1_A3") (pintype "unspecified"))
      (node (ref "USB4") (pin "B3") (pinfunction "SSTXn2_B3") (pintype "unspecified"))
      (node (ref "USB5") (pin "A3") (pinfunction "SSTXn1_A3") (pintype "unspecified"))
      (node (ref "USB5") (pin "B3") (pinfunction "SSTXn2_B3") (pintype "unspecified"))
      (node (ref "USB6") (pin "A3") (pinfunction "SSTXn1_A3") (pintype "unspecified"))
      (node (ref "USB6") (pin "B3") (pinfunction "SSTXn2_B3") (pintype "unspecified"))
      (node (ref "USB7") (pin "A3") (pinfunction "SSTXn1_A3") (pintype "unspecified"))
      (node (ref "USB7") (pin "B3") (pinfunction "SSTXn2_B3") (pintype "unspecified"))
      (node (ref "USB8") (pin "A3") (pinfunction "SSTXn1_A3") (pintype "unspecified"))
      (node (ref "USB8") (pin "B3") (pinfunction "SSTXn2_B3") (pintype "unspecified"))
      (node (ref "USB9") (pin "A3") (pinfunction "SSTXn1_A3") (pintype "unspecified"))
      (node (ref "USB9") (pin "B3") (pinfunction "SSTXn2_B3") (pintype "unspecified"))
    )
    (net (code "22") (name "/SWDIO_3") (class "Default")
      (node (ref "USB1") (pin "A2") (pinfunction "SSTXP1_A2") (pintype "unspecified"))
      (node (ref "USB1") (pin "B2") (pinfunction "SSTXp2_B2") (pintype "unspecified"))
      (node (ref "USB10") (pin "A2") (pinfunction "SSTXP1_A2") (pintype "unspecified"))
      (node (ref "USB10") (pin "B2") (pinfunction "SSTXp2_B2") (pintype "unspecified"))
      (node (ref "USB11") (pin "A2") (pinfunction "SSTXP1_A2") (pintype "unspecified"))
      (node (ref "USB11") (pin "B2") (pinfunction "SSTXp2_B2") (pintype "unspecified"))
      (node (ref "USB12") (pin "A2") (pinfunction "SSTXP1_A2") (pintype "unspecified"))
      (node (ref "USB12") (pin "B2") (pinfunction "SSTXp2_B2") (pintype "unspecified"))
      (node (ref "USB13") (pin "A2") (pinfunction "SSTXP1_A2") (pintype "unspecified"))
      (node (ref "USB13") (pin "B2") (pinfunction "SSTXp2_B2") (pintype "unspecified"))
      (node (ref "USB14") (pin "A2") (pinfunction "SSTXP1_A2") (pintype "unspecified"))
      (node (ref "USB14") (pin "B2") (pinfunction "SSTXp2_B2") (pintype "unspecified"))
      (node (ref "USB15") (pin "A2") (pinfunction "SSTXP1_A2") (pintype "unspecified"))
      (node (ref "USB15") (pin "B2") (pinfunction "SSTXp2_B2") (pintype "unspecified"))
      (node (ref "USB16") (pin "A2") (pinfunction "SSTXP1_A2") (pintype "unspecified"))
      (node (ref "USB16") (pin "B2") (pinfunction "SSTXp2_B2") (pintype "unspecified"))
      (node (ref "USB2") (pin "A2") (pinfunction "SSTXP1_A2") (pintype "unspecified"))
      (node (ref "USB2") (pin "B2") (pinfunction "SSTXp2_B2") (pintype "unspecified"))
      (node (ref "USB3") (pin "A2") (pinfunction "SSTXP1_A2") (pintype "unspecified"))
      (node (ref "USB3") (pin "B2") (pinfunction "SSTXp2_B2") (pintype "unspecified"))
      (node (ref "USB4") (pin "A2") (pinfunction "SSTXP1_A2") (pintype "unspecified"))
      (node (ref "USB4") (pin "B2") (pinfunction "SSTXp2_B2") (pintype "unspecified"))
      (node (ref "USB5") (pin "A2") (pinfunction "SSTXP1_A2") (pintype "unspecified"))
      (node (ref "USB5") (pin "B2") (pinfunction "SSTXp2_B2") (pintype "unspecified"))
      (node (ref "USB6") (pin "A2") (pinfunction "SSTXP1_A2") (pintype "unspecified"))
      (node (ref "USB6") (pin "B2") (pinfunction "SSTXp2_B2") (pintype "unspecified"))
      (node (ref "USB7") (pin "A2") (pinfunction "SSTXP1_A2") (pintype "unspecified"))
      (node (ref "USB7") (pin "B2") (pinfunction "SSTXp2_B2") (pintype "unspecified"))
      (node (ref "USB8") (pin "A2") (pinfunction "SSTXP1_A2") (pintype "unspecified"))
      (node (ref "USB8") (pin "B2") (pinfunction "SSTXp2_B2") (pintype "unspecified"))
      (node (ref "USB9") (pin "A2") (pinfunction "SSTXP1_A2") (pintype "unspecified"))
      (node (ref "USB9") (pin "B2") (pinfunction "SSTXp2_B2") (pintype "unspecified"))
    )
    (net (code "23") (name "/VCC3_3V") (class "Default")
      (node (ref "USB1") (pin "A10") (pinfunction "SSRXn2_A10") (pintype "unspecified"))
      (node (ref "USB1") (pin "B10") (pinfunction "SSRXn1_B10") (pintype "unspecified"))
      (node (ref "USB10") (pin "A10") (pinfunction "SSRXn2_A10") (pintype "unspecified"))
      (node (ref "USB10") (pin "B10") (pinfunction "SSRXn1_B10") (pintype "unspecified"))
      (node (ref "USB11") (pin "A10") (pinfunction "SSRXn2_A10") (pintype "unspecified"))
      (node (ref "USB11") (pin "B10") (pinfunction "SSRXn1_B10") (pintype "unspecified"))
      (node (ref "USB12") (pin "A10") (pinfunction "SSRXn2_A10") (pintype "unspecified"))
      (node (ref "USB12") (pin "B10") (pinfunction "SSRXn1_B10") (pintype "unspecified"))
      (node (ref "USB13") (pin "A10") (pinfunction "SSRXn2_A10") (pintype "unspecified"))
      (node (ref "USB13") (pin "B10") (pinfunction "SSRXn1_B10") (pintype "unspecified"))
      (node (ref "USB14") (pin "A10") (pinfunction "SSRXn2_A10") (pintype "unspecified"))
      (node (ref "USB14") (pin "B10") (pinfunction "SSRXn1_B10") (pintype "unspecified"))
      (node (ref "USB15") (pin "A10") (pinfunction "SSRXn2_A10") (pintype "unspecified"))
      (node (ref "USB15") (pin "B10") (pinfunction "SSRXn1_B10") (pintype "unspecified"))
      (node (ref "USB16") (pin "A10") (pinfunction "SSRXn2_A10") (pintype "unspecified"))
      (node (ref "USB16") (pin "B10") (pinfunction "SSRXn1_B10") (pintype "unspecified"))
      (node (ref "USB2") (pin "A10") (pinfunction "SSRXn2_A10") (pintype "unspecified"))
      (node (ref "USB2") (pin "B10") (pinfunction "SSRXn1_B10") (pintype "unspecified"))
      (node (ref "USB3") (pin "A10") (pinfunction "SSRXn2_A10") (pintype "unspecified"))
      (node (ref "USB3") (pin "B10") (pinfunction "SSRXn1_B10") (pintype "unspecified"))
      (node (ref "USB4") (pin "A10") (pinfunction "SSRXn2_A10") (pintype "unspecified"))
      (node (ref "USB4") (pin "B10") (pinfunction "SSRXn1_B10") (pintype "unspecified"))
      (node (ref "USB5") (pin "A10") (pinfunction "SSRXn2_A10") (pintype "unspecified"))
      (node (ref "USB5") (pin "B10") (pinfunction "SSRXn1_B10") (pintype "unspecified"))
      (node (ref "USB6") (pin "A10") (pinfunction "SSRXn2_A10") (pintype "unspecified"))
      (node (ref "USB6") (pin "B10") (pinfunction "SSRXn1_B10") (pintype "unspecified"))
      (node (ref "USB7") (pin "A10") (pinfunction "SSRXn2_A10") (pintype "unspecified"))
      (node (ref "USB7") (pin "B10") (pinfunction "SSRXn1_B10") (pintype "unspecified"))
      (node (ref "USB8") (pin "A10") (pinfunction "SSRXn2_A10") (pintype "unspecified"))
      (node (ref "USB8") (pin "B10") (pinfunction "SSRXn1_B10") (pintype "unspecified"))
      (node (ref "USB9") (pin "A10") (pinfunction "SSRXn2_A10") (pintype "unspecified"))
      (node (ref "USB9") (pin "B10") (pinfunction "SSRXn1_B10") (pintype "unspecified"))
    )
    (net (code "24") (name "/VIN") (class "Default")
      (node (ref "CN1") (pin "2") (pinfunction "+_2") (pintype "unspecified"))
      (node (ref "USB1") (pin "A4") (pinfunction "VBUS_A4") (pintype "unspecified"))
      (node (ref "USB1") (pin "A9") (pinfunction "VBUS_A9") (pintype "unspecified"))
      (node (ref "USB1") (pin "B4") (pinfunction "VBUS_B4") (pintype "unspecified"))
      (node (ref "USB1") (pin "B9") (pinfunction "VBUS_B9") (pintype "unspecified"))
      (node (ref "USB10") (pin "A4") (pinfunction "VBUS_A4") (pintype "unspecified"))
      (node (ref "USB10") (pin "A9") (pinfunction "VBUS_A9") (pintype "unspecified"))
      (node (ref "USB10") (pin "B4") (pinfunction "VBUS_B4") (pintype "unspecified"))
      (node (ref "USB10") (pin "B9") (pinfunction "VBUS_B9") (pintype "unspecified"))
      (node (ref "USB11") (pin "A4") (pinfunction "VBUS_A4") (pintype "unspecified"))
      (node (ref "USB11") (pin "A9") (pinfunction "VBUS_A9") (pintype "unspecified"))
      (node (ref "USB11") (pin "B4") (pinfunction "VBUS_B4") (pintype "unspecified"))
      (node (ref "USB11") (pin "B9") (pinfunction "VBUS_B9") (pintype "unspecified"))
      (node (ref "USB12") (pin "A4") (pinfunction "VBUS_A4") (pintype "unspecified"))
      (node (ref "USB12") (pin "A9") (pinfunction "VBUS_A9") (pintype "unspecified"))
      (node (ref "USB12") (pin "B4") (pinfunction "VBUS_B4") (pintype "unspecified"))
      (node (ref "USB12") (pin "B9") (pinfunction "VBUS_B9") (pintype "unspecified"))
      (node (ref "USB13") (pin "A4") (pinfunction "VBUS_A4") (pintype "unspecified"))
      (node (ref "USB13") (pin "A9") (pinfunction "VBUS_A9") (pintype "unspecified"))
      (node (ref "USB13") (pin "B4") (pinfunction "VBUS_B4") (pintype "unspecified"))
      (node (ref "USB13") (pin "B9") (pinfunction "VBUS_B9") (pintype "unspecified"))
      (node (ref "USB14") (pin "A4") (pinfunction "VBUS_A4") (pintype "unspecified"))
      (node (ref "USB14") (pin "A9") (pinfunction "VBUS_A9") (pintype "unspecified"))
      (node (ref "USB14") (pin "B4") (pinfunction "VBUS_B4") (pintype "unspecified"))
      (node (ref "USB14") (pin "B9") (pinfunction "VBUS_B9") (pintype "unspecified"))
      (node (ref "USB15") (pin "A4") (pinfunction "VBUS_A4") (pintype "unspecified"))
      (node (ref "USB15") (pin "A9") (pinfunction "VBUS_A9") (pintype "unspecified"))
      (node (ref "USB15") (pin "B4") (pinfunction "VBUS_B4") (pintype "unspecified"))
      (node (ref "USB15") (pin "B9") (pinfunction "VBUS_B9") (pintype "unspecified"))
      (node (ref "USB16") (pin "A4") (pinfunction "VBUS_A4") (pintype "unspecified"))
      (node (ref "USB16") (pin "A9") (pinfunction "VBUS_A9") (pintype "unspecified"))
      (node (ref "USB16") (pin "B4") (pinfunction "VBUS_B4") (pintype "unspecified"))
      (node (ref "USB16") (pin "B9") (pinfunction "VBUS_B9") (pintype "unspecified"))
      (node (ref "USB2") (pin "A4") (pinfunction "VBUS_A4") (pintype "unspecified"))
      (node (ref "USB2") (pin "A9") (pinfunction "VBUS_A9") (pintype "unspecified"))
      (node (ref "USB2") (pin "B4") (pinfunction "VBUS_B4") (pintype "unspecified"))
      (node (ref "USB2") (pin "B9") (pinfunction "VBUS_B9") (pintype "unspecified"))
      (node (ref "USB3") (pin "A4") (pinfunction "VBUS_A4") (pintype "unspecified"))
      (node (ref "USB3") (pin "A9") (pinfunction "VBUS_A9") (pintype "unspecified"))
      (node (ref "USB3") (pin "B4") (pinfunction "VBUS_B4") (pintype "unspecified"))
      (node (ref "USB3") (pin "B9") (pinfunction "VBUS_B9") (pintype "unspecified"))
      (node (ref "USB4") (pin "A4") (pinfunction "VBUS_A4") (pintype "unspecified"))
      (node (ref "USB4") (pin "A9") (pinfunction "VBUS_A9") (pintype "unspecified"))
      (node (ref "USB4") (pin "B4") (pinfunction "VBUS_B4") (pintype "unspecified"))
      (node (ref "USB4") (pin "B9") (pinfunction "VBUS_B9") (pintype "unspecified"))
      (node (ref "USB5") (pin "A4") (pinfunction "VBUS_A4") (pintype "unspecified"))
      (node (ref "USB5") (pin "A9") (pinfunction "VBUS_A9") (pintype "unspecified"))
      (node (ref "USB5") (pin "B4") (pinfunction "VBUS_B4") (pintype "unspecified"))
      (node (ref "USB5") (pin "B9") (pinfunction "VBUS_B9") (pintype "unspecified"))
      (node (ref "USB6") (pin "A4") (pinfunction "VBUS_A4") (pintype "unspecified"))
      (node (ref "USB6") (pin "A9") (pinfunction "VBUS_A9") (pintype "unspecified"))
      (node (ref "USB6") (pin "B4") (pinfunction "VBUS_B4") (pintype "unspecified"))
      (node (ref "USB6") (pin "B9") (pinfunction "VBUS_B9") (pintype "unspecified"))
      (node (ref "USB7") (pin "A4") (pinfunction "VBUS_A4") (pintype "unspecified"))
      (node (ref "USB7") (pin "A9") (pinfunction "VBUS_A9") (pintype "unspecified"))
      (node (ref "USB7") (pin "B4") (pinfunction "VBUS_B4") (pintype "unspecified"))
      (node (ref "USB7") (pin "B9") (pinfunction "VBUS_B9") (pintype "unspecified"))
      (node (ref "USB8") (pin "A4") (pinfunction "VBUS_A4") (pintype "unspecified"))
      (node (ref "USB8") (pin "A9") (pinfunction "VBUS_A9") (pintype "unspecified"))
      (node (ref "USB8") (pin "B4") (pinfunction "VBUS_B4") (pintype "unspecified"))
      (node (ref "USB8") (pin "B9") (pinfunction "VBUS_B9") (pintype "unspecified"))
      (node (ref "USB9") (pin "A4") (pinfunction "VBUS_A4") (pintype "unspecified"))
      (node (ref "USB9") (pin "A9") (pinfunction "VBUS_A9") (pintype "unspecified"))
      (node (ref "USB9") (pin "B4") (pinfunction "VBUS_B4") (pintype "unspecified"))
      (node (ref "USB9") (pin "B9") (pinfunction "VBUS_B9") (pintype "unspecified"))
    )
    (net (code "25") (name "GND") (class "Default")
      (node (ref "CN1") (pin "1") (pinfunction "-_1") (pintype "unspecified"))
      (node (ref "R1") (pin "2") (pinfunction "2_2") (pintype "input"))
      (node (ref "R10") (pin "2") (pinfunction "2_2") (pintype "input"))
      (node (ref "R11") (pin "2") (pinfunction "2_2") (pintype "input"))
      (node (ref "R12") (pin "2") (pinfunction "2_2") (pintype "input"))
      (node (ref "R13") (pin "2") (pinfunction "2_2") (pintype "input"))
      (node (ref "R14") (pin "2") (pinfunction "2_2") (pintype "input"))
      (node (ref "R15") (pin "2") (pinfunction "2_2") (pintype "input"))
      (node (ref "R16") (pin "2") (pinfunction "2_2") (pintype "input"))
      (node (ref "R2") (pin "2") (pinfunction "2_2") (pintype "input"))
      (node (ref "R3") (pin "2") (pinfunction "2_2") (pintype "input"))
      (node (ref "R4") (pin "2") (pinfunction "2_2") (pintype "input"))
      (node (ref "R5") (pin "2") (pinfunction "2_2") (pintype "input"))
      (node (ref "R6") (pin "2") (pinfunction "2_2") (pintype "input"))
      (node (ref "R7") (pin "2") (pinfunction "2_2") (pintype "input"))
      (node (ref "R8") (pin "2") (pinfunction "2_2") (pintype "input"))
      (node (ref "R9") (pin "2") (pinfunction "2_2") (pintype "input"))
      (node (ref "USB1") (pin "A1") (pinfunction "GND_A1") (pintype "unspecified"))
      (node (ref "USB1") (pin "A12") (pinfunction "GND_A12") (pintype "unspecified"))
      (node (ref "USB1") (pin "B1") (pinfunction "GND_B1") (pintype "unspecified"))
      (node (ref "USB1") (pin "B12") (pinfunction "GND_B12") (pintype "unspecified"))
      (node (ref "USB10") (pin "A1") (pinfunction "GND_A1") (pintype "unspecified"))
      (node (ref "USB10") (pin "A12") (pinfunction "GND_A12") (pintype "unspecified"))
      (node (ref "USB10") (pin "B1") (pinfunction "GND_B1") (pintype "unspecified"))
      (node (ref "USB10") (pin "B12") (pinfunction "GND_B12") (pintype "unspecified"))
      (node (ref "USB11") (pin "A1") (pinfunction "GND_A1") (pintype "unspecified"))
      (node (ref "USB11") (pin "A12") (pinfunction "GND_A12") (pintype "unspecified"))
      (node (ref "USB11") (pin "B1") (pinfunction "GND_B1") (pintype "unspecified"))
      (node (ref "USB11") (pin "B12") (pinfunction "GND_B12") (pintype "unspecified"))
      (node (ref "USB12") (pin "A1") (pinfunction "GND_A1") (pintype "unspecified"))
      (node (ref "USB12") (pin "A12") (pinfunction "GND_A12") (pintype "unspecified"))
      (node (ref "USB12") (pin "B1") (pinfunction "GND_B1") (pintype "unspecified"))
      (node (ref "USB12") (pin "B12") (pinfunction "GND_B12") (pintype "unspecified"))
      (node (ref "USB13") (pin "A1") (pinfunction "GND_A1") (pintype "unspecified"))
      (node (ref "USB13") (pin "A12") (pinfunction "GND_A12") (pintype "unspecified"))
      (node (ref "USB13") (pin "B1") (pinfunction "GND_B1") (pintype "unspecified"))
      (node (ref "USB13") (pin "B12") (pinfunction "GND_B12") (pintype "unspecified"))
      (node (ref "USB14") (pin "A1") (pinfunction "GND_A1") (pintype "unspecified"))
      (node (ref "USB14") (pin "A12") (pinfunction "GND_A12") (pintype "unspecified"))
      (node (ref "USB14") (pin "B1") (pinfunction "GND_B1") (pintype "unspecified"))
      (node (ref "USB14") (pin "B12") (pinfunction "GND_B12") (pintype "unspecified"))
      (node (ref "USB15") (pin "A1") (pinfunction "GND_A1") (pintype "unspecified"))
      (node (ref "USB15") (pin "A12") (pinfunction "GND_A12") (pintype "unspecified"))
      (node (ref "USB15") (pin "B1") (pinfunction "GND_B1") (pintype "unspecified"))
      (node (ref "USB15") (pin "B12") (pinfunction "GND_B12") (pintype "unspecified"))
      (node (ref "USB16") (pin "A1") (pinfunction "GND_A1") (pintype "unspecified"))
      (node (ref "USB16") (pin "A12") (pinfunction "GND_A12") (pintype "unspecified"))
      (node (ref "USB16") (pin "B1") (pinfunction "GND_B1") (pintype "unspecified"))
      (node (ref "USB16") (pin "B12") (pinfunction "GND_B12") (pintype "unspecified"))
      (node (ref "USB2") (pin "A1") (pinfunction "GND_A1") (pintype "unspecified"))
      (node (ref "USB2") (pin "A12") (pinfunction "GND_A12") (pintype "unspecified"))
      (node (ref "USB2") (pin "B1") (pinfunction "GND_B1") (pintype "unspecified"))
      (node (ref "USB2") (pin "B12") (pinfunction "GND_B12") (pintype "unspecified"))
      (node (ref "USB3") (pin "A1") (pinfunction "GND_A1") (pintype "unspecified"))
      (node (ref "USB3") (pin "A12") (pinfunction "GND_A12") (pintype "unspecified"))
      (node (ref "USB3") (pin "B1") (pinfunction "GND_B1") (pintype "unspecified"))
      (node (ref "USB3") (pin "B12") (pinfunction "GND_B12") (pintype "unspecified"))
      (node (ref "USB4") (pin "A1") (pinfunction "GND_A1") (pintype "unspecified"))
      (node (ref "USB4") (pin "A12") (pinfunction "GND_A12") (pintype "unspecified"))
      (node (ref "USB4") (pin "B1") (pinfunction "GND_B1") (pintype "unspecified"))
      (node (ref "USB4") (pin "B12") (pinfunction "GND_B12") (pintype "unspecified"))
      (node (ref "USB5") (pin "A1") (pinfunction "GND_A1") (pintype "unspecified"))
      (node (ref "USB5") (pin "A12") (pinfunction "GND_A12") (pintype "unspecified"))
      (node (ref "USB5") (pin "B1") (pinfunction "GND_B1") (pintype "unspecified"))
      (node (ref "USB5") (pin "B12") (pinfunction "GND_B12") (pintype "unspecified"))
      (node (ref "USB6") (pin "A1") (pinfunction "GND_A1") (pintype "unspecified"))
      (node (ref "USB6") (pin "A12") (pinfunction "GND_A12") (pintype "unspecified"))
      (node (ref "USB6") (pin "B1") (pinfunction "GND_B1") (pintype "unspecified"))
      (node (ref "USB6") (pin "B12") (pinfunction "GND_B12") (pintype "unspecified"))
      (node (ref "USB7") (pin "A1") (pinfunction "GND_A1") (pintype "unspecified"))
      (node (ref "USB7") (pin "A12") (pinfunction "GND_A12") (pintype "unspecified"))
      (node (ref "USB7") (pin "B1") (pinfunction "GND_B1") (pintype "unspecified"))
      (node (ref "USB7") (pin "B12") (pinfunction "GND_B12") (pintype "unspecified"))
      (node (ref "USB8") (pin "A1") (pinfunction "GND_A1") (pintype "unspecified"))
      (node (ref "USB8") (pin "A12") (pinfunction "GND_A12") (pintype "unspecified"))
      (node (ref "USB8") (pin "B1") (pinfunction "GND_B1") (pintype "unspecified"))
      (node (ref "USB8") (pin "B12") (pinfunction "GND_B12") (pintype "unspecified"))
      (node (ref "USB9") (pin "A1") (pinfunction "GND_A1") (pintype "unspecified"))
      (node (ref "USB9") (pin "A12") (pinfunction "GND_A12") (pintype "unspecified"))
      (node (ref "USB9") (pin "B1") (pinfunction "GND_B1") (pintype "unspecified"))
      (node (ref "USB9") (pin "B12") (pinfunction "GND_B12") (pintype "unspecified"))
    )
    (net (code "26") (name "Net-(LED1-C)") (class "Default")
      (node (ref "LED1") (pin "1") (pinfunction "C_1") (pintype "input"))
      (node (ref "R1") (pin "1") (pinfunction "1_1") (pintype "input"))
    )
    (net (code "27") (name "Net-(LED2-C)") (class "Default")
      (node (ref "LED2") (pin "1") (pinfunction "C_1") (pintype "input"))
      (node (ref "R2") (pin "1") (pinfunction "1_1") (pintype "input"))
    )
    (net (code "28") (name "Net-(LED3-C)") (class "Default")
      (node (ref "LED3") (pin "1") (pinfunction "C_1") (pintype "input"))
      (node (ref "R3") (pin "1") (pinfunction "1_1") (pintype "input"))
    )
    (net (code "29") (name "Net-(LED4-C)") (class "Default")
      (node (ref "LED4") (pin "1") (pinfunction "C_1") (pintype "input"))
      (node (ref "R4") (pin "1") (pinfunction "1_1") (pintype "input"))
    )
    (net (code "30") (name "Net-(LED5-C)") (class "Default")
      (node (ref "LED5") (pin "1") (pinfunction "C_1") (pintype "input"))
      (node (ref "R5") (pin "1") (pinfunction "1_1") (pintype "input"))
    )
    (net (code "31") (name "Net-(LED6-C)") (class "Default")
      (node (ref "LED6") (pin "1") (pinfunction "C_1") (pintype "input"))
      (node (ref "R6") (pin "1") (pinfunction "1_1") (pintype "input"))
    )
    (net (code "32") (name "Net-(LED7-C)") (class "Default")
      (node (ref "LED7") (pin "1") (pinfunction "C_1") (pintype "input"))
      (node (ref "R7") (pin "1") (pinfunction "1_1") (pintype "input"))
    )
    (net (code "33") (name "Net-(LED8-C)") (class "Default")
      (node (ref "LED8") (pin "1") (pinfunction "C_1") (pintype "input"))
      (node (ref "R8") (pin "1") (pinfunction "1_1") (pintype "input"))
    )
    (net (code "34") (name "Net-(LED9-C)") (class "Default")
      (node (ref "LED9") (pin "1") (pinfunction "C_1") (pintype "input"))
      (node (ref "R9") (pin "1") (pinfunction "1_1") (pintype "input"))
    )
    (net (code "35") (name "Net-(LED10-C)") (class "Default")
      (node (ref "LED10") (pin "1") (pinfunction "C_1") (pintype "input"))
      (node (ref "R10") (pin "1") (pinfunction "1_1") (pintype "input"))
    )
    (net (code "36") (name "Net-(LED11-C)") (class "Default")
      (node (ref "LED11") (pin "1") (pinfunction "C_1") (pintype "input"))
      (node (ref "R11") (pin "1") (pinfunction "1_1") (pintype "input"))
    )
    (net (code "37") (name "Net-(LED12-C)") (class "Default")
      (node (ref "LED12") (pin "1") (pinfunction "C_1") (pintype "input"))
      (node (ref "R12") (pin "1") (pinfunction "1_1") (pintype "input"))
    )
    (net (code "38") (name "Net-(LED13-C)") (class "Default")
      (node (ref "LED13") (pin "1") (pinfunction "C_1") (pintype "input"))
      (node (ref "R13") (pin "1") (pinfunction "1_1") (pintype "input"))
    )
    (net (code "39") (name "Net-(LED14-C)") (class "Default")
      (node (ref "LED14") (pin "1") (pinfunction "C_1") (pintype "input"))
      (node (ref "R14") (pin "1") (pinfunction "1_1") (pintype "input"))
    )
    (net (code "40") (name "Net-(LED15-C)") (class "Default")
      (node (ref "LED15") (pin "1") (pinfunction "C_1") (pintype "input"))
      (node (ref "R15") (pin "1") (pinfunction "1_1") (pintype "input"))
    )
    (net (code "41") (name "Net-(LED16-C)") (class "Default")
      (node (ref "LED16") (pin "1") (pinfunction "C_1") (pintype "input"))
      (node (ref "R16") (pin "1") (pinfunction "1_1") (pintype "input"))
    )
    (net (code "42") (name "unconnected-(CN1-Pad3)") (class "Default")
      (node (ref "CN1") (pin "3") (pinfunction "3_3") (pintype "unspecified+no_connect"))
    )
    (net (code "43") (name "unconnected-(CN1-Pad4)") (class "Default")
      (node (ref "CN1") (pin "4") (pinfunction "4_4") (pintype "unspecified+no_connect"))
    )
    (net (code "44") (name "unconnected-(USB1-EH-Pad25)") (class "Default")
      (node (ref "USB1") (pin "25") (pinfunction "EH_25") (pintype "unspecified+no_connect"))
    )
    (net (code "45") (name "unconnected-(USB2-EH-Pad25)") (class "Default")
      (node (ref "USB2") (pin "25") (pinfunction "EH_25") (pintype "unspecified+no_connect"))
    )
    (net (code "46") (name "unconnected-(USB3-EH-Pad25)") (class "Default")
      (node (ref "USB3") (pin "25") (pinfunction "EH_25") (pintype "unspecified+no_connect"))
    )
    (net (code "47") (name "unconnected-(USB4-EH-Pad25)") (class "Default")
      (node (ref "USB4") (pin "25") (pinfunction "EH_25") (pintype "unspecified+no_connect"))
    )
    (net (code "48") (name "unconnected-(USB5-EH-Pad25)") (class "Default")
      (node (ref "USB5") (pin "25") (pinfunction "EH_25") (pintype "unspecified+no_connect"))
    )
    (net (code "49") (name "unconnected-(USB6-EH-Pad25)") (class "Default")
      (node (ref "USB6") (pin "25") (pinfunction "EH_25") (pintype "unspecified+no_connect"))
    )
    (net (code "50") (name "unconnected-(USB7-EH-Pad25)") (class "Default")
      (node (ref "USB7") (pin "25") (pinfunction "EH_25") (pintype "unspecified+no_connect"))
    )
    (net (code "51") (name "unconnected-(USB8-EH-Pad25)") (class "Default")
      (node (ref "USB8") (pin "25") (pinfunction "EH_25") (pintype "unspecified+no_connect"))
    )
    (net (code "52") (name "unconnected-(USB9-EH-Pad25)") (class "Default")
      (node (ref "USB9") (pin "25") (pinfunction "EH_25") (pintype "unspecified+no_connect"))
    )
    (net (code "53") (name "unconnected-(USB10-EH-Pad25)") (class "Default")
      (node (ref "USB10") (pin "25") (pinfunction "EH_25") (pintype "unspecified+no_connect"))
    )
    (net (code "54") (name "unconnected-(USB11-EH-Pad25)") (class "Default")
      (node (ref "USB11") (pin "25") (pinfunction "EH_25") (pintype "unspecified+no_connect"))
    )
    (net (code "55") (name "unconnected-(USB12-EH-Pad25)") (class "Default")
      (node (ref "USB12") (pin "25") (pinfunction "EH_25") (pintype "unspecified+no_connect"))
    )
    (net (code "56") (name "unconnected-(USB13-EH-Pad25)") (class "Default")
      (node (ref "USB13") (pin "25") (pinfunction "EH_25") (pintype "unspecified+no_connect"))
    )
    (net (code "57") (name "unconnected-(USB14-EH-Pad25)") (class "Default")
      (node (ref "USB14") (pin "25") (pinfunction "EH_25") (pintype "unspecified+no_connect"))
    )
    (net (code "58") (name "unconnected-(USB15-EH-Pad25)") (class "Default")
      (node (ref "USB15") (pin "25") (pinfunction "EH_25") (pintype "unspecified+no_connect"))
    )
    (net (code "59") (name "unconnected-(USB16-EH-Pad25)") (class "Default")
      (node (ref "USB16") (pin "25") (pinfunction "EH_25") (pintype "unspecified+no_connect"))
    )
  )
)
